# Dual_linear_VCA_chip_v3_0_-_external_tri.net
KiCad netlist of a schematic drawn in EAGLE
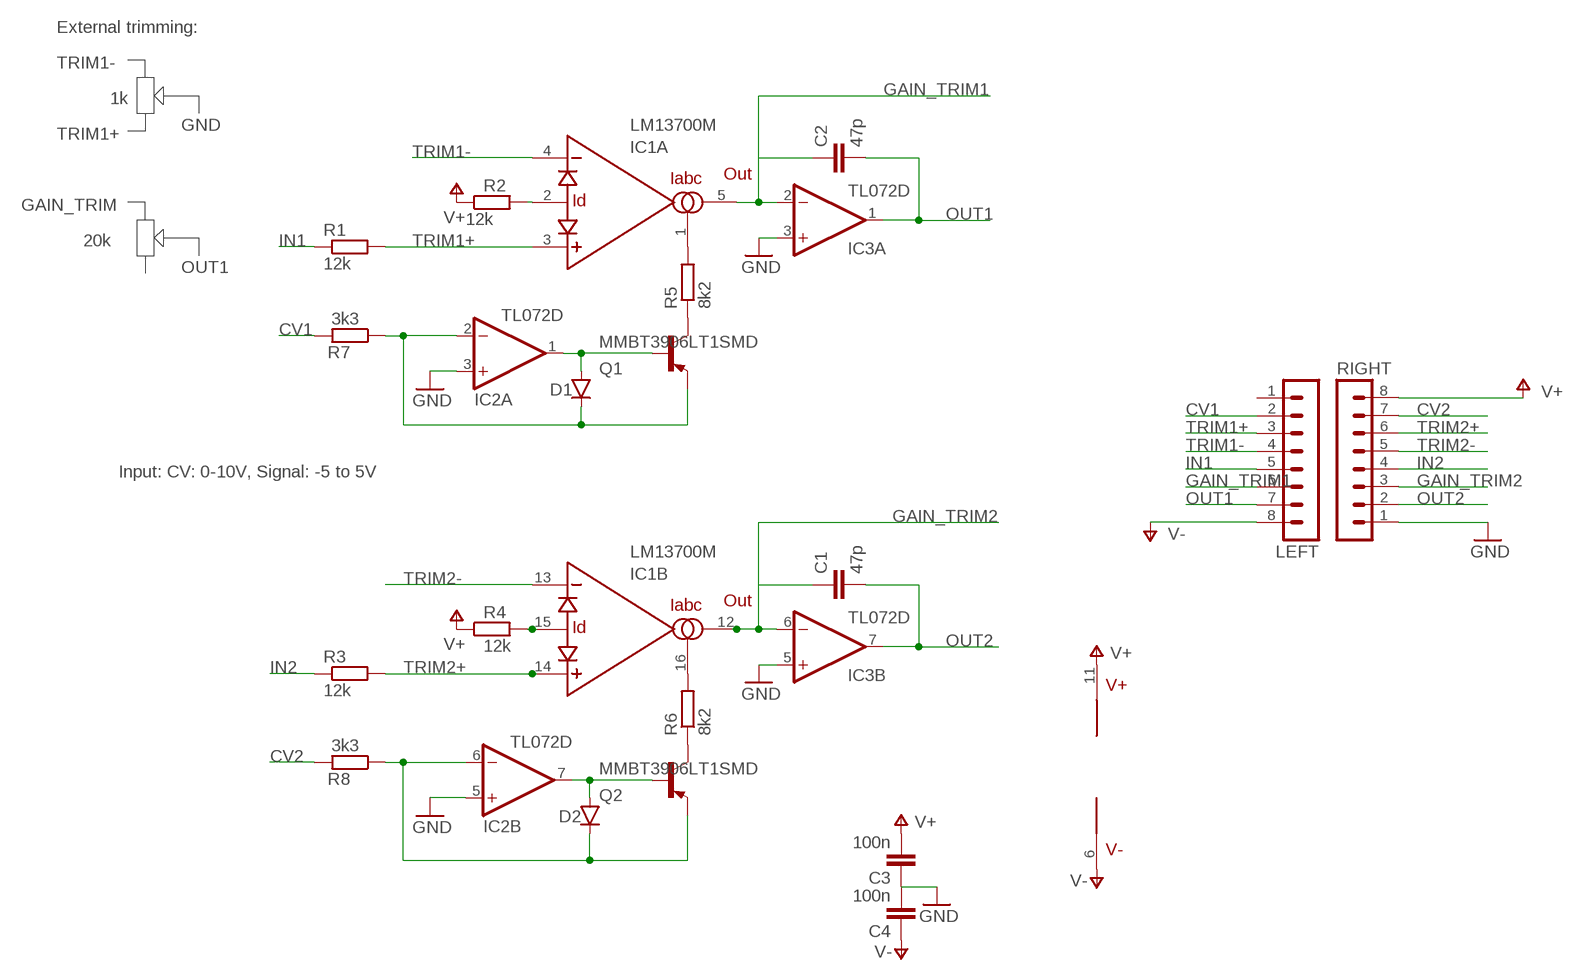
[diagram p0: schematic, sheet 1]

(export (version "E")
  (design (tool "Eeschema 10.0.6"))
  (components
    (comp (ref "C1")
      (value "47p")
      (footprint "eagle-import:C0805")
      (libsource (lib "eagle-import") (part "C-EUC0805"))
    )
    (comp (ref "C2")
      (value "47p")
      (footprint "eagle-import:C0805")
      (libsource (lib "eagle-import") (part "C-EUC0805"))
    )
    (comp (ref "C3")
      (value "100n")
      (footprint "eagle-import:C0805")
      (libsource (lib "eagle-import") (part "C-EUC0805"))
    )
    (comp (ref "C4")
      (value "100n")
      (footprint "eagle-import:C0805")
      (libsource (lib "eagle-import") (part "C-EUC0805"))
    )
    (comp (ref "D1")
      (value "1N41480805")
      (footprint "eagle-import:D0805-J")
      (libsource (lib "eagle-import") (part "1N41480805"))
    )
    (comp (ref "D2")
      (value "1N41480805")
      (footprint "eagle-import:D0805-J")
      (libsource (lib "eagle-import") (part "1N41480805"))
    )
    (comp (ref "IC1")
      (value "LM13700M")
      (footprint "eagle-import:SO16")
      (libsource (lib "eagle-import") (part "LM13700M"))
    )
    (comp (ref "IC2")
      (value "TL072D")
      (footprint "eagle-import:SO08")
      (libsource (lib "eagle-import") (part "TL072D"))
    )
    (comp (ref "IC3")
      (value "TL072D")
      (footprint "eagle-import:SO08")
      (libsource (lib "eagle-import") (part "TL072D"))
    )
    (comp (ref "LEFT")
      (value "MA08-1JC")
      (footprint "eagle-import:MA08-1J")
      (libsource (lib "eagle-import") (part "MA08-1JC"))
    )
    (comp (ref "Q1")
      (value "MMBT3906LT1SMD")
      (footprint "eagle-import:SOT23-BEC")
      (libsource (lib "eagle-import") (part "MMBT3906SMDLT1"))
    )
    (comp (ref "Q2")
      (value "MMBT3906LT1SMD")
      (footprint "eagle-import:SOT23-BEC")
      (libsource (lib "eagle-import") (part "MMBT3906SMDLT1"))
    )
    (comp (ref "R1")
      (value "12k")
      (footprint "eagle-import:R0805")
      (libsource (lib "eagle-import") (part "R-EU_R0805"))
    )
    (comp (ref "R2")
      (value "12k")
      (footprint "eagle-import:R0805")
      (libsource (lib "eagle-import") (part "R-EU_R0805"))
    )
    (comp (ref "R3")
      (value "12k")
      (footprint "eagle-import:R0805")
      (libsource (lib "eagle-import") (part "R-EU_R0805"))
    )
    (comp (ref "R4")
      (value "12k")
      (footprint "eagle-import:R0805")
      (libsource (lib "eagle-import") (part "R-EU_R0805"))
    )
    (comp (ref "R5")
      (value "8k2")
      (footprint "eagle-import:R0805")
      (libsource (lib "eagle-import") (part "R-EU_R0805"))
    )
    (comp (ref "R6")
      (value "8k2")
      (footprint "eagle-import:R0805")
      (libsource (lib "eagle-import") (part "R-EU_R0805"))
    )
    (comp (ref "R7")
      (value "3k3")
      (footprint "eagle-import:R0805")
      (libsource (lib "eagle-import") (part "R-EU_R0805"))
    )
    (comp (ref "R8")
      (value "3k3")
      (footprint "eagle-import:R0805")
      (libsource (lib "eagle-import") (part "R-EU_R0805"))
    )
    (comp (ref "RIGHT")
      (value "MA08-1JC")
      (footprint "eagle-import:MA08-1J")
      (libsource (lib "eagle-import") (part "MA08-1JC"))
    )
  )
  (nets
    (net (code "1") (name "/CV1") (class "Default")
      (node (ref "LEFT") (pin "2") (pinfunction "2_2") (pintype "passive"))
      (node (ref "R7") (pin "2") (pinfunction "2_2") (pintype "passive"))
    )
    (net (code "2") (name "/CV2") (class "Default")
      (node (ref "R8") (pin "2") (pinfunction "2_2") (pintype "passive"))
      (node (ref "RIGHT") (pin "7") (pinfunction "7_7") (pintype "passive"))
    )
    (net (code "3") (name "/GAIN_TRIM1") (class "Default")
      (node (ref "C2") (pin "1") (pinfunction "1_1") (pintype "passive"))
      (node (ref "IC1") (pin "5") (pinfunction "OUT_5") (pintype "bidirectional"))
      (node (ref "IC3") (pin "2") (pinfunction "-IN_2") (pintype "input"))
      (node (ref "LEFT") (pin "6") (pinfunction "6_6") (pintype "passive"))
    )
    (net (code "4") (name "/GAIN_TRIM2") (class "Default")
      (node (ref "C1") (pin "1") (pinfunction "1_1") (pintype "passive"))
      (node (ref "IC1") (pin "12") (pinfunction "OUT_12") (pintype "bidirectional"))
      (node (ref "IC3") (pin "6") (pinfunction "-IN_6") (pintype "input"))
      (node (ref "RIGHT") (pin "3") (pinfunction "3_3") (pintype "passive"))
    )
    (net (code "5") (name "/IN1") (class "Default")
      (node (ref "LEFT") (pin "5") (pinfunction "5_5") (pintype "passive"))
      (node (ref "R1") (pin "1") (pinfunction "1_1") (pintype "passive"))
    )
    (net (code "6") (name "/IN2") (class "Default")
      (node (ref "R3") (pin "1") (pinfunction "1_1") (pintype "passive"))
      (node (ref "RIGHT") (pin "4") (pinfunction "4_4") (pintype "passive"))
    )
    (net (code "7") (name "/OUT1") (class "Default")
      (node (ref "C2") (pin "2") (pinfunction "2_2") (pintype "passive"))
      (node (ref "IC3") (pin "1") (pinfunction "OUT_1") (pintype "output"))
      (node (ref "LEFT") (pin "7") (pinfunction "7_7") (pintype "passive"))
    )
    (net (code "8") (name "/OUT2") (class "Default")
      (node (ref "C1") (pin "2") (pinfunction "2_2") (pintype "passive"))
      (node (ref "IC3") (pin "7") (pinfunction "OUT_7") (pintype "output"))
      (node (ref "RIGHT") (pin "2") (pinfunction "2_2") (pintype "passive"))
    )
    (net (code "9") (name "/TRIM1+") (class "Default")
      (node (ref "IC1") (pin "3") (pinfunction "+IN_3") (pintype "bidirectional"))
      (node (ref "LEFT") (pin "3") (pinfunction "3_3") (pintype "passive"))
      (node (ref "R1") (pin "2") (pinfunction "2_2") (pintype "passive"))
    )
    (net (code "10") (name "/TRIM1-") (class "Default")
      (node (ref "IC1") (pin "4") (pinfunction "-IN_4") (pintype "bidirectional"))
      (node (ref "LEFT") (pin "4") (pinfunction "4_4") (pintype "passive"))
    )
    (net (code "11") (name "/TRIM2+") (class "Default")
      (node (ref "IC1") (pin "14") (pinfunction "+IN_14") (pintype "bidirectional"))
      (node (ref "R3") (pin "2") (pinfunction "2_2") (pintype "passive"))
      (node (ref "RIGHT") (pin "6") (pinfunction "6_6") (pintype "passive"))
    )
    (net (code "12") (name "/TRIM2-") (class "Default")
      (node (ref "IC1") (pin "13") (pinfunction "-IN_13") (pintype "bidirectional"))
      (node (ref "RIGHT") (pin "5") (pinfunction "5_5") (pintype "passive"))
    )
    (net (code "13") (name "GND") (class "Default")
      (node (ref "C3") (pin "1") (pinfunction "1_1") (pintype "passive"))
      (node (ref "C4") (pin "2") (pinfunction "2_2") (pintype "passive"))
      (node (ref "IC2") (pin "3") (pinfunction "+IN_3") (pintype "input"))
      (node (ref "IC2") (pin "5") (pinfunction "+IN_5") (pintype "input"))
      (node (ref "IC3") (pin "3") (pinfunction "+IN_3") (pintype "input"))
      (node (ref "IC3") (pin "5") (pinfunction "+IN_5") (pintype "input"))
      (node (ref "RIGHT") (pin "1") (pinfunction "1_1") (pintype "passive"))
    )
    (net (code "14") (name "Net-(IC1A-IABC)") (class "Default")
      (node (ref "IC1") (pin "1") (pinfunction "IABC_1") (pintype "bidirectional"))
      (node (ref "R5") (pin "2") (pinfunction "2_2") (pintype "passive"))
    )
    (net (code "15") (name "Net-(IC1A-ID)") (class "Default")
      (node (ref "IC1") (pin "2") (pinfunction "ID_2") (pintype "bidirectional"))
      (node (ref "R2") (pin "2") (pinfunction "2_2") (pintype "passive"))
    )
    (net (code "16") (name "Net-(IC1B-IABC)") (class "Default")
      (node (ref "IC1") (pin "16") (pinfunction "IABC_16") (pintype "bidirectional"))
      (node (ref "R6") (pin "2") (pinfunction "2_2") (pintype "passive"))
    )
    (net (code "17") (name "Net-(IC1B-ID)") (class "Default")
      (node (ref "IC1") (pin "15") (pinfunction "ID_15") (pintype "bidirectional"))
      (node (ref "R4") (pin "2") (pinfunction "2_2") (pintype "passive"))
    )
    (net (code "18") (name "Net-(IC2A--IN)") (class "Default")
      (node (ref "D1") (pin "C") (pinfunction "C_C") (pintype "passive"))
      (node (ref "IC2") (pin "2") (pinfunction "-IN_2") (pintype "input"))
      (node (ref "Q1") (pin "E") (pinfunction "E_E") (pintype "passive"))
      (node (ref "R7") (pin "1") (pinfunction "1_1") (pintype "passive"))
    )
    (net (code "19") (name "Net-(IC2A-OUT)") (class "Default")
      (node (ref "D1") (pin "A") (pinfunction "A_A") (pintype "passive"))
      (node (ref "IC2") (pin "1") (pinfunction "OUT_1") (pintype "output"))
      (node (ref "Q1") (pin "B") (pinfunction "B_B") (pintype "passive"))
    )
    (net (code "20") (name "Net-(IC2B--IN)") (class "Default")
      (node (ref "D2") (pin "C") (pinfunction "C_C") (pintype "passive"))
      (node (ref "IC2") (pin "6") (pinfunction "-IN_6") (pintype "input"))
      (node (ref "Q2") (pin "E") (pinfunction "E_E") (pintype "passive"))
      (node (ref "R8") (pin "1") (pinfunction "1_1") (pintype "passive"))
    )
    (net (code "21") (name "Net-(IC2B-OUT)") (class "Default")
      (node (ref "D2") (pin "A") (pinfunction "A_A") (pintype "passive"))
      (node (ref "IC2") (pin "7") (pinfunction "OUT_7") (pintype "output"))
      (node (ref "Q2") (pin "B") (pinfunction "B_B") (pintype "passive"))
    )
    (net (code "22") (name "Net-(Q1-PadC)") (class "Default")
      (node (ref "Q1") (pin "C") (pinfunction "C_C") (pintype "passive"))
      (node (ref "R5") (pin "1") (pinfunction "1_1") (pintype "passive"))
    )
    (net (code "23") (name "Net-(Q2-PadC)") (class "Default")
      (node (ref "Q2") (pin "C") (pinfunction "C_C") (pintype "passive"))
      (node (ref "R6") (pin "1") (pinfunction "1_1") (pintype "passive"))
    )
    (net (code "24") (name "V+") (class "Default")
      (node (ref "C3") (pin "2") (pinfunction "2_2") (pintype "passive"))
      (node (ref "IC1") (pin "11") (pinfunction "V+_11") (pintype "bidirectional"))
      (node (ref "R2") (pin "1") (pinfunction "1_1") (pintype "passive"))
      (node (ref "R4") (pin "1") (pinfunction "1_1") (pintype "passive"))
      (node (ref "RIGHT") (pin "8") (pinfunction "8_8") (pintype "passive"))
    )
    (net (code "25") (name "V-") (class "Default")
      (node (ref "C4") (pin "1") (pinfunction "1_1") (pintype "passive"))
      (node (ref "IC1") (pin "6") (pinfunction "V-_6") (pintype "bidirectional"))
      (node (ref "LEFT") (pin "8") (pinfunction "8_8") (pintype "passive"))
    )
    (net (code "26") (name "unconnected-(LEFT-Pad1)") (class "Default")
      (node (ref "LEFT") (pin "1") (pinfunction "1_1") (pintype "passive"))
    )
  )
)
